# ClientMainBoard.net
KiCad netlist of a schematic drawn in Altium Designer
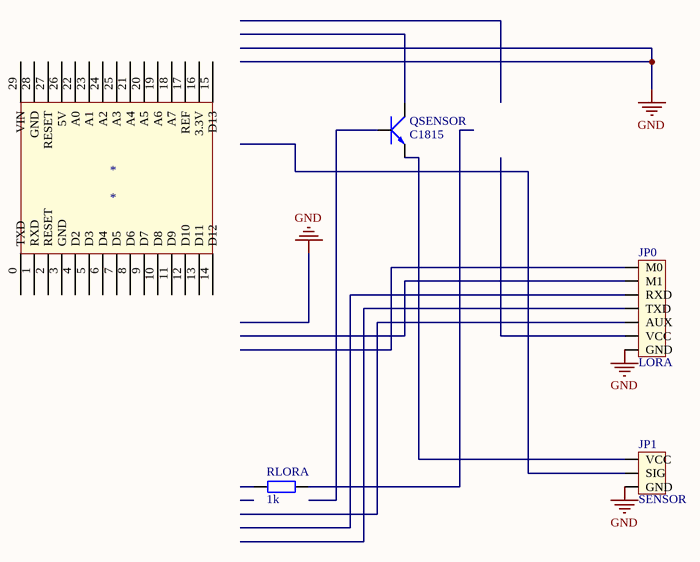
[diagram p0: ClientMainBoard.SchDoc]

(export (version "E")
  (design (tool "Eeschema 10.0.6"))
  (components
    (comp (ref "*") (value "*") (footprint "Arduino nano") (libsource (lib "*") (part "arduinoNano")))
    (comp (ref "JP0")
      (value "LORA")
      (footprint "CON7")
      (description "Connector 7")
      (libsource (lib "syhaunguyen") (part "Con7"))
    )
    (comp (ref "JP1")
      (value "SENSOR")
      (footprint "CON3")
      (description "Connector 3")
      (libsource (lib "syhaunguyen") (part "Con3"))
    )
    (comp (ref "QSENSOR")
      (value "C1815")
      (footprint "QTO-92")
      (description "NPN 600mW, ECB")
      (libsource (lib "syhaunguyen") (part "C1815"))
    )
    (comp (ref "RLORA")
      (value "1k")
      (footprint "R1/4W")
      (description "Resistor 1/4W")
      (libsource (lib "syhaunguyen") (part "R1/4W"))
    )
  )
  (nets
    (net (code "1") (name "GND") (class "Default")
      (node (ref "JP0") (pin "7") (pinfunction "GND_7") (pintype "passive"))
      (node (ref "JP1") (pin "3") (pinfunction "GND_3") (pintype "passive"))
    )
    (net (code "2") (name "Net-(JP1-VCC)") (class "Default")
      (node (ref "JP1") (pin "1") (pinfunction "VCC_1") (pintype "passive"))
      (node (ref "QSENSOR") (pin "1") (pinfunction "E_1") (pintype "passive"))
    )
    (net (code "3") (name "unconnected-(*-3.3V-Pad16)") (class "Default")
      (node (ref "*") (pin "16") (pinfunction "3.3V_16") (pintype "passive"))
    )
    (net (code "4") (name "unconnected-(*-5V-Pad26)") (class "Default")
      (node (ref "*") (pin "26") (pinfunction "5V_26") (pintype "passive"))
    )
    (net (code "5") (name "unconnected-(*-A0-Pad22)") (class "Default")
      (node (ref "*") (pin "22") (pinfunction "A0_22") (pintype "passive"))
    )
    (net (code "6") (name "unconnected-(*-A1-Pad23)") (class "Default")
      (node (ref "*") (pin "23") (pinfunction "A1_23") (pintype "passive"))
    )
    (net (code "7") (name "unconnected-(*-A2-Pad24)") (class "Default")
      (node (ref "*") (pin "24") (pinfunction "A2_24") (pintype "passive"))
    )
    (net (code "8") (name "unconnected-(*-A3-Pad25)") (class "Default")
      (node (ref "*") (pin "25") (pinfunction "A3_25") (pintype "passive"))
    )
    (net (code "9") (name "unconnected-(*-A4-Pad21)") (class "Default")
      (node (ref "*") (pin "21") (pinfunction "A4_21") (pintype "passive"))
    )
    (net (code "10") (name "unconnected-(*-A5-Pad20)") (class "Default")
      (node (ref "*") (pin "20") (pinfunction "A5_20") (pintype "passive"))
    )
    (net (code "11") (name "unconnected-(*-A6-Pad19)") (class "Default")
      (node (ref "*") (pin "19") (pinfunction "A6_19") (pintype "passive"))
    )
    (net (code "12") (name "unconnected-(*-A7-Pad18)") (class "Default")
      (node (ref "*") (pin "18") (pinfunction "A7_18") (pintype "passive"))
    )
    (net (code "13") (name "unconnected-(*-D2-Pad4)") (class "Default")
      (node (ref "*") (pin "4") (pinfunction "D2_4") (pintype "passive"))
    )
    (net (code "14") (name "unconnected-(*-D3-Pad5)") (class "Default")
      (node (ref "*") (pin "5") (pinfunction "D3_5") (pintype "passive"))
    )
    (net (code "15") (name "unconnected-(*-D4-Pad6)") (class "Default")
      (node (ref "*") (pin "6") (pinfunction "D4_6") (pintype "passive"))
    )
    (net (code "16") (name "unconnected-(*-D5-Pad7)") (class "Default")
      (node (ref "*") (pin "7") (pinfunction "D5_7") (pintype "passive"))
    )
    (net (code "17") (name "unconnected-(*-D6-Pad8)") (class "Default")
      (node (ref "*") (pin "8") (pinfunction "D6_8") (pintype "passive"))
    )
    (net (code "18") (name "unconnected-(*-D7-Pad9)") (class "Default")
      (node (ref "*") (pin "9") (pinfunction "D7_9") (pintype "passive"))
    )
    (net (code "19") (name "unconnected-(*-D8-Pad10)") (class "Default")
      (node (ref "*") (pin "10") (pinfunction "D8_10") (pintype "passive"))
    )
    (net (code "20") (name "unconnected-(*-D9-Pad11)") (class "Default")
      (node (ref "*") (pin "11") (pinfunction "D9_11") (pintype "passive"))
    )
    (net (code "21") (name "unconnected-(*-D10-Pad12)") (class "Default")
      (node (ref "*") (pin "12") (pinfunction "D10_12") (pintype "passive"))
    )
    (net (code "22") (name "unconnected-(*-D11-Pad13)") (class "Default")
      (node (ref "*") (pin "13") (pinfunction "D11_13") (pintype "passive"))
    )
    (net (code "23") (name "unconnected-(*-D12-Pad14)") (class "Default")
      (node (ref "*") (pin "14") (pinfunction "D12_14") (pintype "passive"))
    )
    (net (code "24") (name "unconnected-(*-D13-Pad15)") (class "Default")
      (node (ref "*") (pin "15") (pinfunction "D13_15") (pintype "passive"))
    )
    (net (code "25") (name "unconnected-(*-GND-Pad3)") (class "Default")
      (node (ref "*") (pin "3") (pinfunction "GND_3") (pintype "passive"))
    )
    (net (code "26") (name "unconnected-(*-GND-Pad28)") (class "Default")
      (node (ref "*") (pin "28") (pinfunction "GND_28") (pintype "passive"))
    )
    (net (code "27") (name "unconnected-(*-REF-Pad17)") (class "Default")
      (node (ref "*") (pin "17") (pinfunction "REF_17") (pintype "passive"))
    )
    (net (code "28") (name "unconnected-(*-RESET-Pad2)") (class "Default")
      (node (ref "*") (pin "2") (pinfunction "RESET_2") (pintype "passive"))
    )
    (net (code "29") (name "unconnected-(*-RESET-Pad27)") (class "Default")
      (node (ref "*") (pin "27") (pinfunction "RESET_27") (pintype "passive"))
    )
    (net (code "30") (name "unconnected-(*-RXD-Pad1)") (class "Default")
      (node (ref "*") (pin "1") (pinfunction "RXD_1") (pintype "passive"))
    )
    (net (code "31") (name "unconnected-(*-TXD-Pad0)") (class "Default")
      (node (ref "*") (pin "0") (pinfunction "TXD_0") (pintype "passive"))
    )
    (net (code "32") (name "unconnected-(*-VIN-Pad29)") (class "Default")
      (node (ref "*") (pin "29") (pinfunction "VIN_29") (pintype "passive"))
    )
    (net (code "33") (name "unconnected-(JP0-AUX-Pad5)") (class "Default")
      (node (ref "JP0") (pin "5") (pinfunction "AUX_5") (pintype "passive"))
    )
    (net (code "34") (name "unconnected-(JP0-M0-Pad1)") (class "Default")
      (node (ref "JP0") (pin "1") (pinfunction "M0_1") (pintype "passive"))
    )
    (net (code "35") (name "unconnected-(JP0-M1-Pad2)") (class "Default")
      (node (ref "JP0") (pin "2") (pinfunction "M1_2") (pintype "passive"))
    )
    (net (code "36") (name "unconnected-(JP0-RXD-Pad3)") (class "Default")
      (node (ref "JP0") (pin "3") (pinfunction "RXD_3") (pintype "passive"))
    )
    (net (code "37") (name "unconnected-(JP0-TXD-Pad4)") (class "Default")
      (node (ref "JP0") (pin "4") (pinfunction "TXD_4") (pintype "passive"))
    )
    (net (code "38") (name "unconnected-(JP0-VCC-Pad6)") (class "Default")
      (node (ref "JP0") (pin "6") (pinfunction "VCC_6") (pintype "passive"))
    )
    (net (code "39") (name "unconnected-(JP1-SIG-Pad2)") (class "Default")
      (node (ref "JP1") (pin "2") (pinfunction "SIG_2") (pintype "passive"))
    )
    (net (code "40") (name "unconnected-(QSENSOR-B-Pad3)") (class "Default")
      (node (ref "QSENSOR") (pin "3") (pinfunction "B_3") (pintype "passive"))
    )
    (net (code "41") (name "unconnected-(QSENSOR-C-Pad2)") (class "Default")
      (node (ref "QSENSOR") (pin "2") (pinfunction "C_2") (pintype "passive"))
    )
    (net (code "42") (name "unconnected-(RLORA-Pad1)") (class "Default")
      (node (ref "RLORA") (pin "1") (pinfunction "1_1") (pintype "passive"))
    )
    (net (code "43") (name "unconnected-(RLORA-Pad2)") (class "Default")
      (node (ref "RLORA") (pin "2") (pinfunction "2_2") (pintype "passive"))
    )
  )
)
